# ProPrj_odin-core_2026-06-12.net
KiCad netlist of a schematic drawn in EasyEDA Pro
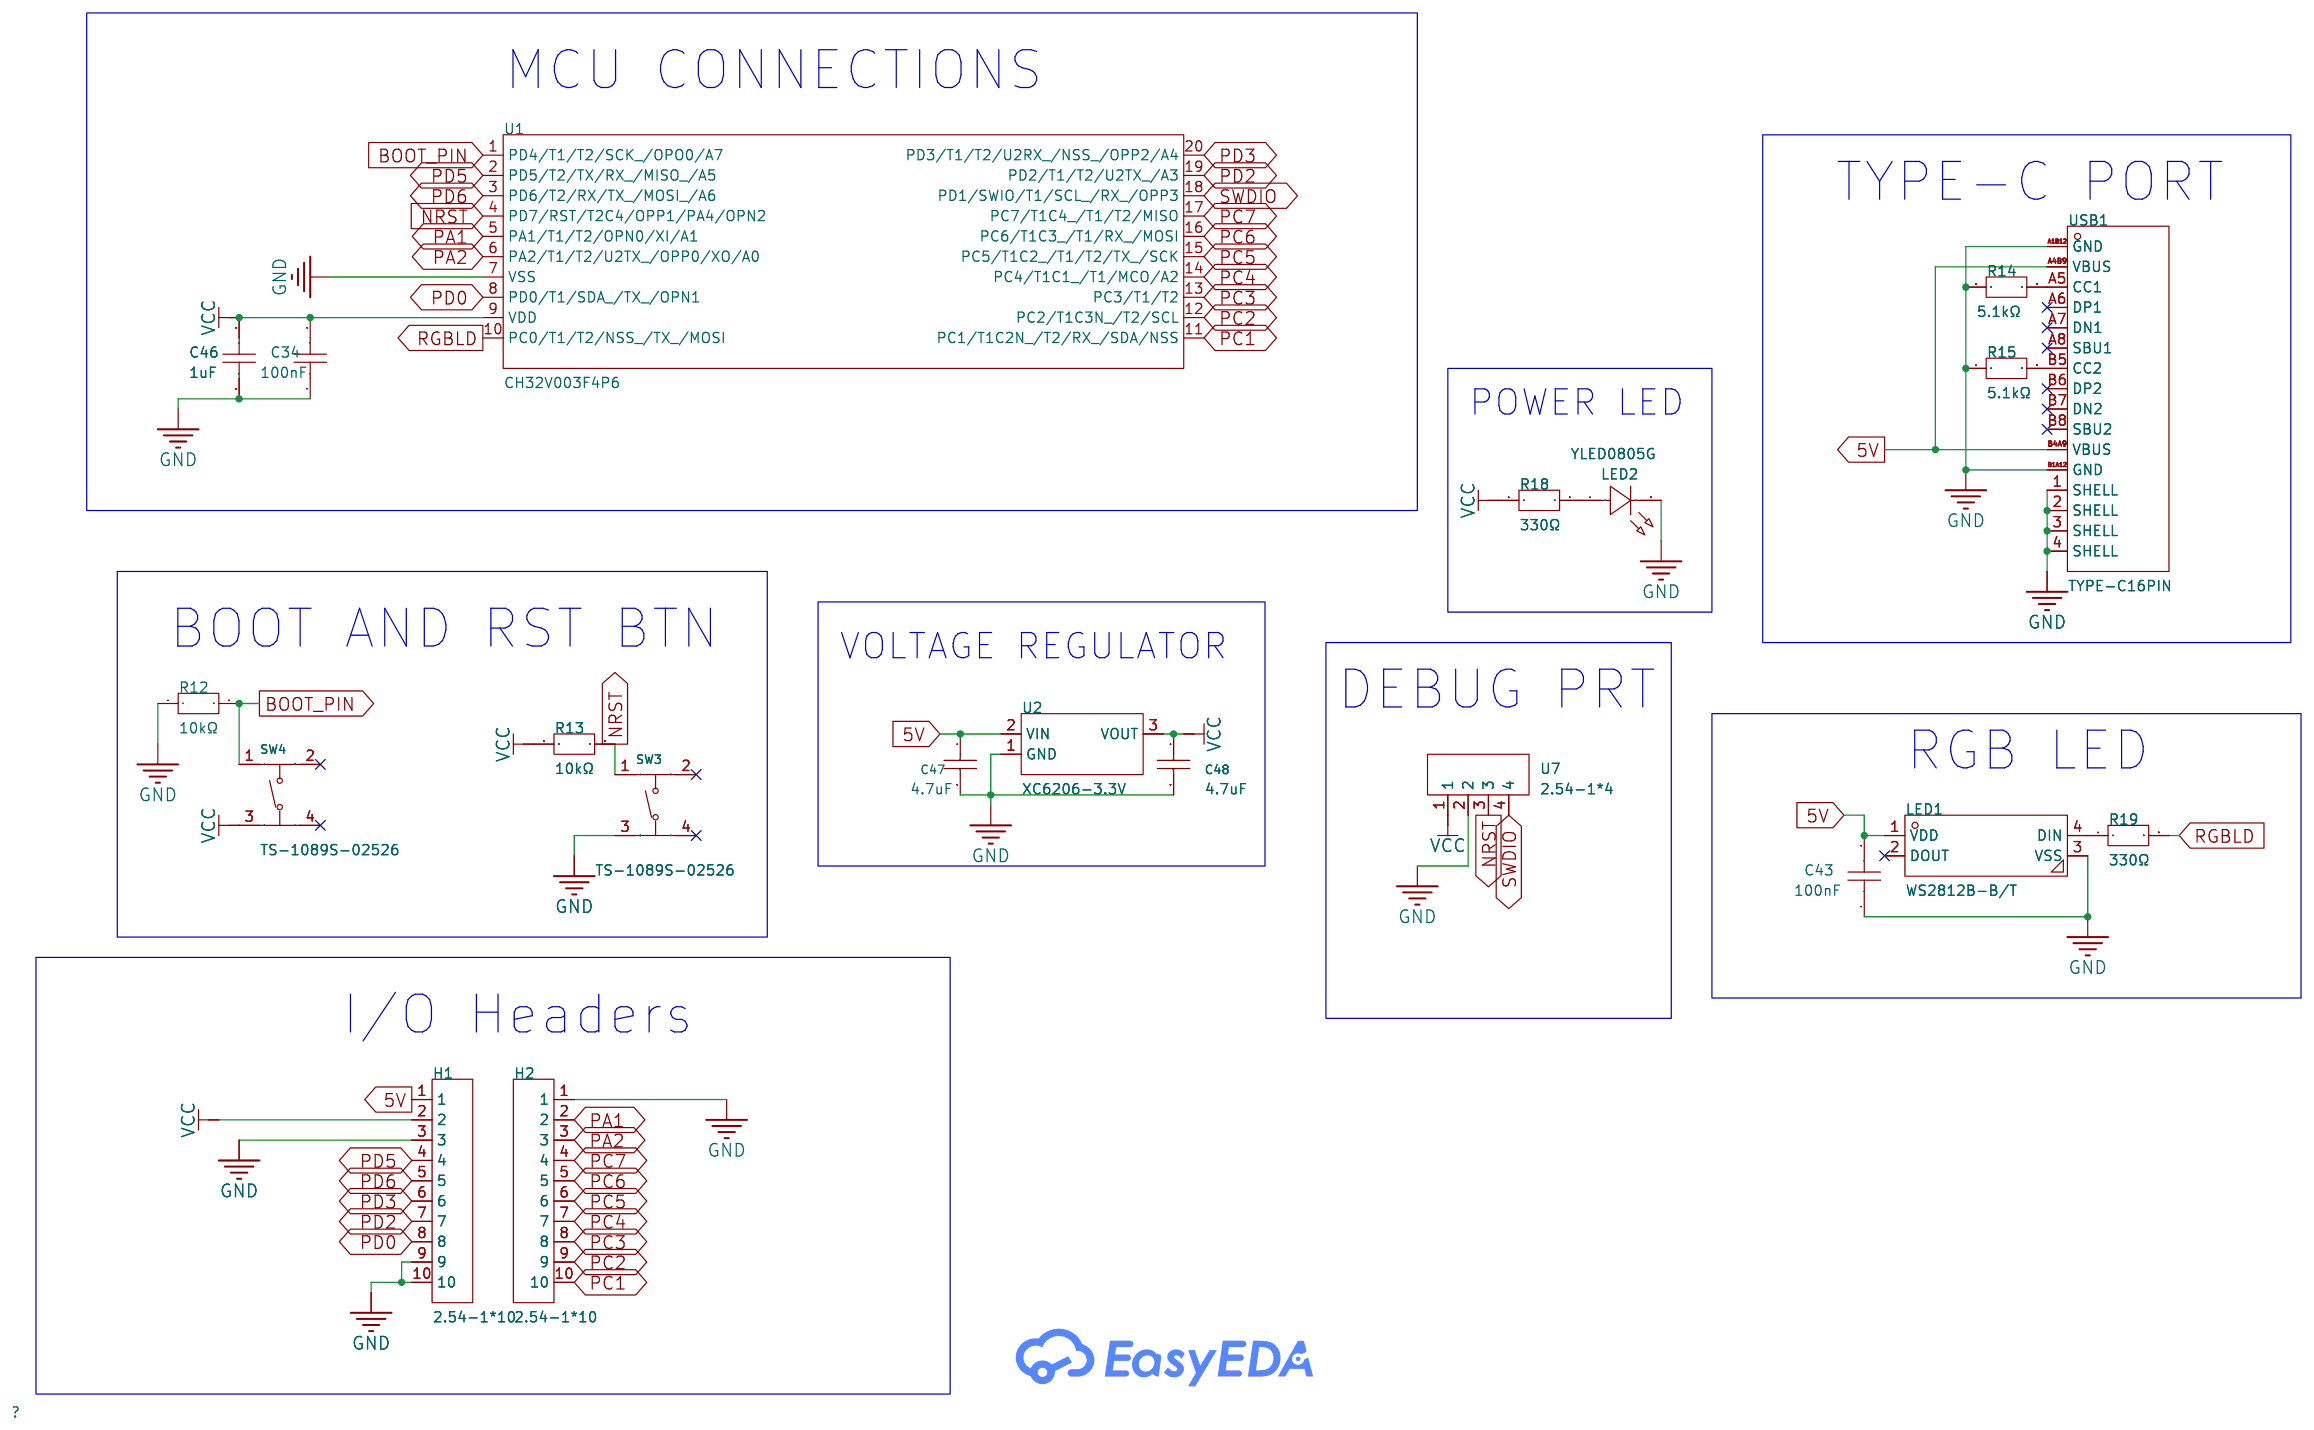
[diagram p0: schematic sheet]

(export (version "E")
  (design (tool "Eeschema 10.0.6"))
  (components
    (comp (ref "C34")
      (value "100nF")
      (footprint "easyedapro:C0603")
      (description "Capacitance:100nF Tolerance:±10% Tolerance:±10% Voltage Rating:50V Temperature Coefficient:X7R")
      (fields
        (field (name "Manufacturer Part") "FCC0603B104K500CT")
        (field (name "Manufacturer") "FOJAN(富捷)")
      )
      (libsource (lib "easyedapro") (part "FCC0603B104K500CT"))
    )
    (comp (ref "C43")
      (value "100nF")
      (footprint "easyedapro:C0603")
      (description "Capacitance:100nF Tolerance:±10% Tolerance:±10% Voltage Rating:50V Temperature Coefficient:X7R")
      (fields
        (field (name "Manufacturer Part") "FCC0603B104K500CT")
        (field (name "Manufacturer") "FOJAN(富捷)")
      )
      (libsource (lib "easyedapro") (part "FCC0603B104K500CT"))
    )
    (comp (ref "C46")
      (value "1uF")
      (footprint "easyedapro:C0603")
      (description "Capacitance:1uF Tolerance:±10% Tolerance:±10% Voltage Rating:50V Temperature Coefficient:X5R")
      (fields
        (field (name "Manufacturer Part") "CGA0603X5R105K500JT")
        (field (name "Manufacturer") "HRE(芯声)")
      )
      (libsource (lib "easyedapro") (part "CGA0603X5R105K500JT"))
    )
    (comp (ref "C47")
      (value "4.7uF")
      (footprint "easyedapro:C0603")
      (description "Capacitance:4.7uF Tolerance:±10% Tolerance:±10% Voltage Rating:10V Temperature Coefficient:X5R")
      (fields
        (field (name "Manufacturer Part") "CL10A475KP8NNNC")
        (field (name "Manufacturer") "SAMSUNG(三星)")
      )
      (libsource (lib "easyedapro") (part "CL10A475KP8NNNC"))
    )
    (comp (ref "C48")
      (value "4.7uF")
      (footprint "easyedapro:C0603")
      (description "Capacitance:4.7uF Tolerance:±10% Tolerance:±10% Voltage Rating:10V Temperature Coefficient:X5R")
      (fields
        (field (name "Manufacturer Part") "CL10A475KP8NNNC")
        (field (name "Manufacturer") "SAMSUNG(三星)")
      )
      (libsource (lib "easyedapro") (part "CL10A475KP8NNNC"))
    )
    (comp (ref "H1")
      (value "2.54-1*10")
      (footprint "easyedapro:HDR-TH_10P-P2.54-V-M")
      (fields (field (name "Manufacturer") "ZHOURI(洲日)"))
      (libsource (lib "easyedapro") (part "2.54-1*10"))
    )
    (comp (ref "H2")
      (value "2.54-1*10")
      (footprint "easyedapro:HDR-TH_10P-P2.54-V-M")
      (fields (field (name "Manufacturer") "ZHOURI(洲日)"))
      (libsource (lib "easyedapro") (part "2.54-1*10"))
    )
    (comp (ref "LED1")
      (value "WS2812B-B/T")
      (footprint "easyedapro:LED-SMD_4P-L5.0-W5.0-TL_WS2812B-B")
      (fields (field (name "Manufacturer") "worldsemi"))
      (libsource (lib "easyedapro") (part "WS2812B-B/W"))
    )
    (comp (ref "LED2")
      (value "YLED0805G")
      (footprint "easyedapro:LED0805-FD-GREEN")
      (fields (field (name "Manufacturer") "YONGYUTAI(永裕泰)"))
      (libsource (lib "easyedapro") (part "YLED0805G"))
    )
    (comp (ref "R12")
      (value "10kΩ")
      (footprint "easyedapro:R0603")
      (fields (field (name "Manufacturer Part") "FRC0603J103 TS") (field (name "Manufacturer") "FOJAN(富捷)"))
      (libsource (lib "easyedapro") (part "FRC0603J103TS"))
    )
    (comp (ref "R13")
      (value "10kΩ")
      (footprint "easyedapro:R0603")
      (fields (field (name "Manufacturer Part") "FRC0603J103 TS") (field (name "Manufacturer") "FOJAN(富捷)"))
      (libsource (lib "easyedapro") (part "FRC0603J103TS"))
    )
    (comp (ref "R14")
      (value "5.1kΩ")
      (footprint "easyedapro:R0603")
      (fields (field (name "Manufacturer Part") "FRC0603F5101TS") (field (name "Manufacturer") "FOJAN(富捷)"))
      (libsource (lib "easyedapro") (part "FRC0603F5101TS"))
    )
    (comp (ref "R15")
      (value "5.1kΩ")
      (footprint "easyedapro:R0603")
      (fields (field (name "Manufacturer Part") "FRC0603F5101TS") (field (name "Manufacturer") "FOJAN(富捷)"))
      (libsource (lib "easyedapro") (part "FRC0603F5101TS"))
    )
    (comp (ref "R18")
      (value "330Ω")
      (footprint "easyedapro:R0603")
      (fields (field (name "Manufacturer Part") "FRC0603J331 TS") (field (name "Manufacturer") "FOJAN(富捷)"))
      (libsource (lib "easyedapro") (part "FRC0603J331 TS"))
    )
    (comp (ref "R19")
      (value "330Ω")
      (footprint "easyedapro:R0603")
      (fields (field (name "Manufacturer Part") "FRC0603J331 TS") (field (name "Manufacturer") "FOJAN(富捷)"))
      (libsource (lib "easyedapro") (part "FRC0603J331 TS"))
    )
    (comp (ref "SW3")
      (value "TS-1089S-02526")
      (footprint "easyedapro:SW-SMD_4P-L4.2-W3.3-P2.15-LS5.1")
      (fields (field (name "Manufacturer") "XUNPU(讯普)"))
      (libsource (lib "easyedapro") (part "TS-1089S-02526"))
    )
    (comp (ref "SW4")
      (value "TS-1089S-02526")
      (footprint "easyedapro:SW-SMD_4P-L4.2-W3.3-P2.15-LS5.1")
      (fields (field (name "Manufacturer") "XUNPU(讯普)"))
      (libsource (lib "easyedapro") (part "TS-1089S-02526"))
    )
    (comp (ref "U1")
      (value "CH32V003F4P6")
      (footprint "easyedapro:TSSOP-20_L6.5-W4.4-P0.65-LS6.4-BL")
      (fields (field (name "Manufacturer") "WCH(南京沁恒)"))
      (libsource (lib "easyedapro") (part "CH32V006F8P6_C52753342"))
    )
    (comp (ref "U2")
      (value "XC6206-3.3V")
      (footprint "easyedapro:SOT-89-3_L4.3-W2.3-P1.50-LS4.3-BR")
      (description "Features:Short Circuit Protection；Over Current Protection")
      (fields (field (name "Manufacturer") "YONGYUTAI(永裕泰)"))
      (libsource (lib "easyedapro") (part "XC6206-3.3V_C7603199"))
    )
    (comp (ref "U7")
      (value "2.54-1*4")
      (footprint "easyedapro:HDR-TH_4P-P2.54-V-M-1")
      (fields (field (name "Manufacturer") "ZHOURI(洲日)"))
      (libsource (lib "easyedapro") (part "2.54-1*4"))
    )
    (comp (ref "USB1")
      (value "TYPE-C16PIN")
      (footprint "easyedapro:USB-C-SMD_TYPE-C16PIN")
      (fields (field (name "Manufacturer") "SHOU HAN(首韩)"))
      (libsource (lib "easyedapro") (part "TYPE-C16PIN"))
    )
  )
  (nets
    (net (code "1") (name "5V") (class "Default")
      (node (ref "C43") (pin "2") (pinfunction "2_2") (pintype "unspecified"))
      (node (ref "C47") (pin "1") (pinfunction "1_1") (pintype "input"))
      (node (ref "H1") (pin "1") (pinfunction "1_1") (pintype "unspecified"))
      (node (ref "LED1") (pin "1") (pinfunction "VDD_1") (pintype "unspecified"))
      (node (ref "U2") (pin "2") (pinfunction "VIN_2") (pintype "unspecified"))
      (node (ref "USB1") (pin "A4B9") (pinfunction "VBUS_A4B9") (pintype "unspecified"))
      (node (ref "USB1") (pin "B4A9") (pinfunction "VBUS_B4A9") (pintype "unspecified"))
    )
    (net (code "2") (name "BOOT_PIN") (class "Default")
      (node (ref "R12") (pin "2") (pinfunction "2_2") (pintype "unspecified"))
      (node (ref "SW4") (pin "1") (pinfunction "1_1") (pintype "input"))
      (node (ref "U1") (pin "1") (pinfunction "PD4/T1/T2/SCK_/OPO0/A7_1") (pintype "unspecified"))
    )
    (net (code "3") (name "GND") (class "Default")
      (node (ref "C34") (pin "1") (pinfunction "1_1") (pintype "unspecified"))
      (node (ref "C43") (pin "1") (pinfunction "1_1") (pintype "unspecified"))
      (node (ref "C46") (pin "2") (pinfunction "2_2") (pintype "unspecified"))
      (node (ref "C47") (pin "2") (pinfunction "2_2") (pintype "input"))
      (node (ref "C48") (pin "2") (pinfunction "2_2") (pintype "input"))
      (node (ref "H1") (pin "10") (pinfunction "10_10") (pintype "unspecified"))
      (node (ref "H1") (pin "3") (pinfunction "3_3") (pintype "unspecified"))
      (node (ref "H1") (pin "9") (pinfunction "9_9") (pintype "unspecified"))
      (node (ref "H2") (pin "1") (pinfunction "1_1") (pintype "unspecified"))
      (node (ref "LED1") (pin "3") (pinfunction "VSS_3") (pintype "unspecified"))
      (node (ref "LED2") (pin "2") (pinfunction "K_2") (pintype "unspecified"))
      (node (ref "R12") (pin "1") (pinfunction "1_1") (pintype "unspecified"))
      (node (ref "R14") (pin "1") (pinfunction "1_1") (pintype "unspecified"))
      (node (ref "R15") (pin "1") (pinfunction "1_1") (pintype "unspecified"))
      (node (ref "SW3") (pin "3") (pinfunction "3_3") (pintype "input"))
      (node (ref "U1") (pin "7") (pinfunction "VSS_7") (pintype "unspecified"))
      (node (ref "U2") (pin "1") (pinfunction "GND_1") (pintype "unspecified"))
      (node (ref "U7") (pin "2") (pinfunction "2_2") (pintype "unspecified"))
      (node (ref "USB1") (pin "1") (pinfunction "SHELL_1") (pintype "unspecified"))
      (node (ref "USB1") (pin "2") (pinfunction "SHELL_2") (pintype "unspecified"))
      (node (ref "USB1") (pin "3") (pinfunction "SHELL_3") (pintype "unspecified"))
      (node (ref "USB1") (pin "4") (pinfunction "SHELL_4") (pintype "unspecified"))
      (node (ref "USB1") (pin "A1B12") (pinfunction "GND_A1B12") (pintype "unspecified"))
      (node (ref "USB1") (pin "B1A12") (pinfunction "GND_B1A12") (pintype "unspecified"))
    )
    (net (code "4") (name "NRST") (class "Default")
      (node (ref "R13") (pin "2") (pinfunction "2_2") (pintype "unspecified"))
      (node (ref "SW3") (pin "1") (pinfunction "1_1") (pintype "input"))
      (node (ref "U1") (pin "4") (pinfunction "PD7/RST/T2C4/OPP1/PA4/OPN2_4") (pintype "unspecified"))
      (node (ref "U7") (pin "3") (pinfunction "3_3") (pintype "unspecified"))
    )
    (net (code "5") (name "Net-(LED1-DIN)") (class "Default")
      (node (ref "LED1") (pin "4") (pinfunction "DIN_4") (pintype "unspecified"))
      (node (ref "R19") (pin "1") (pinfunction "1_1") (pintype "unspecified"))
    )
    (net (code "6") (name "Net-(LED2-A)") (class "Default")
      (node (ref "LED2") (pin "1") (pinfunction "A_1") (pintype "unspecified"))
      (node (ref "R18") (pin "2") (pinfunction "2_2") (pintype "unspecified"))
    )
    (net (code "7") (name "Net-(USB1-CC1)") (class "Default")
      (node (ref "R14") (pin "2") (pinfunction "2_2") (pintype "unspecified"))
      (node (ref "USB1") (pin "A5") (pinfunction "CC1_A5") (pintype "unspecified"))
    )
    (net (code "8") (name "Net-(USB1-CC2)") (class "Default")
      (node (ref "R15") (pin "2") (pinfunction "2_2") (pintype "unspecified"))
      (node (ref "USB1") (pin "B5") (pinfunction "CC2_B5") (pintype "unspecified"))
    )
    (net (code "9") (name "PA1") (class "Default")
      (node (ref "H2") (pin "2") (pinfunction "2_2") (pintype "unspecified"))
      (node (ref "U1") (pin "5") (pinfunction "PA1/T1/T2/OPN0/XI/A1_5") (pintype "unspecified"))
    )
    (net (code "10") (name "PA2") (class "Default")
      (node (ref "H2") (pin "3") (pinfunction "3_3") (pintype "unspecified"))
      (node (ref "U1") (pin "6") (pinfunction "PA2/T1/T2/U2TX_/OPP0/XO/A0_6") (pintype "unspecified"))
    )
    (net (code "11") (name "PC1") (class "Default")
      (node (ref "H2") (pin "10") (pinfunction "10_10") (pintype "unspecified"))
      (node (ref "U1") (pin "11") (pinfunction "PC1/T1C2N_/T2/RX_/SDA/NSS_11") (pintype "unspecified"))
    )
    (net (code "12") (name "PC2") (class "Default")
      (node (ref "H2") (pin "9") (pinfunction "9_9") (pintype "unspecified"))
      (node (ref "U1") (pin "12") (pinfunction "PC2/T1C3N_/T2/SCL_12") (pintype "unspecified"))
    )
    (net (code "13") (name "PC3") (class "Default")
      (node (ref "H2") (pin "8") (pinfunction "8_8") (pintype "unspecified"))
      (node (ref "U1") (pin "13") (pinfunction "PC3/T1/T2_13") (pintype "unspecified"))
    )
    (net (code "14") (name "PC4") (class "Default")
      (node (ref "H2") (pin "7") (pinfunction "7_7") (pintype "unspecified"))
      (node (ref "U1") (pin "14") (pinfunction "PC4/T1C1_/T1/MCO/A2_14") (pintype "unspecified"))
    )
    (net (code "15") (name "PC5") (class "Default")
      (node (ref "H2") (pin "6") (pinfunction "6_6") (pintype "unspecified"))
      (node (ref "U1") (pin "15") (pinfunction "PC5/T1C2_/T1/T2/TX_/SCK_15") (pintype "unspecified"))
    )
    (net (code "16") (name "PC6") (class "Default")
      (node (ref "H2") (pin "5") (pinfunction "5_5") (pintype "unspecified"))
      (node (ref "U1") (pin "16") (pinfunction "PC6/T1C3_/T1/RX_/MOSI_16") (pintype "unspecified"))
    )
    (net (code "17") (name "PC7") (class "Default")
      (node (ref "H2") (pin "4") (pinfunction "4_4") (pintype "unspecified"))
      (node (ref "U1") (pin "17") (pinfunction "PC7/T1C4_/T1/T2/MISO_17") (pintype "unspecified"))
    )
    (net (code "18") (name "PD0") (class "Default")
      (node (ref "H1") (pin "8") (pinfunction "8_8") (pintype "unspecified"))
      (node (ref "U1") (pin "8") (pinfunction "PD0/T1/SDA_/TX_/OPN1_8") (pintype "unspecified"))
    )
    (net (code "19") (name "PD2") (class "Default")
      (node (ref "H1") (pin "7") (pinfunction "7_7") (pintype "unspecified"))
      (node (ref "U1") (pin "19") (pinfunction "PD2/T1/T2/U2TX_/A3_19") (pintype "unspecified"))
    )
    (net (code "20") (name "PD3") (class "Default")
      (node (ref "H1") (pin "6") (pinfunction "6_6") (pintype "unspecified"))
      (node (ref "U1") (pin "20") (pinfunction "PD3/T1/T2/U2RX_/NSS_/OPP2/A4_20") (pintype "unspecified"))
    )
    (net (code "21") (name "PD5") (class "Default")
      (node (ref "H1") (pin "4") (pinfunction "4_4") (pintype "unspecified"))
      (node (ref "U1") (pin "2") (pinfunction "PD5/T2/TX/RX_/MISO_/A5_2") (pintype "unspecified"))
    )
    (net (code "22") (name "PD6") (class "Default")
      (node (ref "H1") (pin "5") (pinfunction "5_5") (pintype "unspecified"))
      (node (ref "U1") (pin "3") (pinfunction "PD6/T2/RX/TX_/MOSI_/A6_3") (pintype "unspecified"))
    )
    (net (code "23") (name "RGBLD") (class "Default")
      (node (ref "R19") (pin "2") (pinfunction "2_2") (pintype "unspecified"))
      (node (ref "U1") (pin "10") (pinfunction "PC0/T1/T2/NSS_/TX_/MOSI_10") (pintype "unspecified"))
    )
    (net (code "24") (name "SWDIO") (class "Default")
      (node (ref "U1") (pin "18") (pinfunction "PD1/SWIO/T1/SCL_/RX_/OPP3_18") (pintype "unspecified"))
      (node (ref "U7") (pin "4") (pinfunction "4_4") (pintype "unspecified"))
    )
    (net (code "25") (name "VCC") (class "Default")
      (node (ref "C34") (pin "2") (pinfunction "2_2") (pintype "unspecified"))
      (node (ref "C46") (pin "1") (pinfunction "1_1") (pintype "unspecified"))
      (node (ref "C48") (pin "1") (pinfunction "1_1") (pintype "input"))
      (node (ref "H1") (pin "2") (pinfunction "2_2") (pintype "unspecified"))
      (node (ref "R13") (pin "1") (pinfunction "1_1") (pintype "unspecified"))
      (node (ref "R18") (pin "1") (pinfunction "1_1") (pintype "unspecified"))
      (node (ref "SW4") (pin "3") (pinfunction "3_3") (pintype "input"))
      (node (ref "U1") (pin "9") (pinfunction "VDD_9") (pintype "unspecified"))
      (node (ref "U2") (pin "3") (pinfunction "VOUT_3") (pintype "unspecified"))
      (node (ref "U7") (pin "1") (pinfunction "1_1") (pintype "unspecified"))
    )
    (net (code "26") (name "unconnected-(LED1-DOUT-Pad2)") (class "Default")
      (node (ref "LED1") (pin "2") (pinfunction "DOUT_2") (pintype "unspecified+no_connect"))
    )
    (net (code "27") (name "unconnected-(SW3-Pad2)") (class "Default")
      (node (ref "SW3") (pin "2") (pinfunction "2_2") (pintype "input+no_connect"))
    )
    (net (code "28") (name "unconnected-(SW3-Pad4)") (class "Default")
      (node (ref "SW3") (pin "4") (pinfunction "4_4") (pintype "input+no_connect"))
    )
    (net (code "29") (name "unconnected-(SW4-Pad2)") (class "Default")
      (node (ref "SW4") (pin "2") (pinfunction "2_2") (pintype "input+no_connect"))
    )
    (net (code "30") (name "unconnected-(SW4-Pad4)") (class "Default")
      (node (ref "SW4") (pin "4") (pinfunction "4_4") (pintype "input+no_connect"))
    )
    (net (code "31") (name "unconnected-(USB1-DN1-PadA7)") (class "Default")
      (node (ref "USB1") (pin "A7") (pinfunction "DN1_A7") (pintype "unspecified+no_connect"))
    )
    (net (code "32") (name "unconnected-(USB1-DN2-PadB7)") (class "Default")
      (node (ref "USB1") (pin "B7") (pinfunction "DN2_B7") (pintype "unspecified+no_connect"))
    )
    (net (code "33") (name "unconnected-(USB1-DP1-PadA6)") (class "Default")
      (node (ref "USB1") (pin "A6") (pinfunction "DP1_A6") (pintype "unspecified+no_connect"))
    )
    (net (code "34") (name "unconnected-(USB1-DP2-PadB6)") (class "Default")
      (node (ref "USB1") (pin "B6") (pinfunction "DP2_B6") (pintype "unspecified+no_connect"))
    )
    (net (code "35") (name "unconnected-(USB1-SBU1-PadA8)") (class "Default")
      (node (ref "USB1") (pin "A8") (pinfunction "SBU1_A8") (pintype "unspecified+no_connect"))
    )
    (net (code "36") (name "unconnected-(USB1-SBU2-PadB8)") (class "Default")
      (node (ref "USB1") (pin "B8") (pinfunction "SBU2_B8") (pintype "unspecified+no_connect"))
    )
  )
)
